# SY8029AIC-SCH.net
KiCad netlist of a schematic drawn in Altium Designer
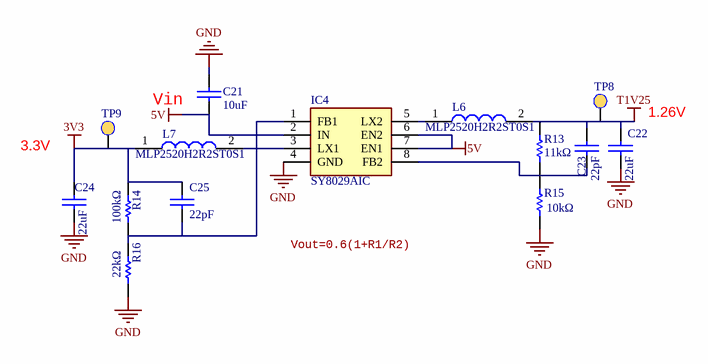
[diagram p0: SY8029AIC-SCH.SchDoc]

(export (version "E")
  (design (tool "Eeschema 10.0.6"))
  (components
    (comp (ref "C21")
      (value "10uF")
      (footprint "C_0805")
      (description "贴片电容")
      (fields (field (name "MANUFACTURER_PART_NUMBER") "±10% /25V"))
      (libsource (lib "IntLib-Passive") (part "Cap_Chip"))
    )
    (comp (ref "C22")
      (value "22uF")
      (footprint "C_0603")
      (description "贴片电容")
      (fields (field (name "MANUFACTURER_PART_NUMBER") "±10% /25V"))
      (libsource (lib "IntLib-Passive") (part "Cap_Chip"))
    )
    (comp (ref "C23")
      (value "22pF")
      (footprint "C_0402")
      (description "贴片电容")
      (fields (field (name "MANUFACTURER_PART_NUMBER") "±10% /25V"))
      (libsource (lib "IntLib-Passive") (part "Cap_Chip"))
    )
    (comp (ref "C24")
      (value "22uF")
      (footprint "C_0603")
      (description "贴片电容")
      (fields (field (name "MANUFACTURER_PART_NUMBER") "±10% /25V"))
      (libsource (lib "IntLib-Passive") (part "Cap_Chip"))
    )
    (comp (ref "C25")
      (value "22pF")
      (footprint "C_0402")
      (description "贴片电容")
      (fields (field (name "MANUFACTURER_PART_NUMBER") "±10% /25V"))
      (libsource (lib "IntLib-Passive") (part "Cap_Chip"))
    )
    (comp (ref "IC4")
      (value "SY8029AIC")
      (footprint "SOT23-8")
      (description "DC-DC降压芯片")
      (libsource (lib "IntLib-IC") (part "SY8029AIC"))
    )
    (comp (ref "L6")
      (value "MLP2520H2R2ST0S1")
      (footprint "INDC2520X100N")
      (description "Inductor")
      (fields (field (name "MANUFACTURER_PART_NUMBER") "MLP2520K1R0MT0S1"))
      (libsource (lib "*") (part "MLP2520K1R0MT0S1"))
    )
    (comp (ref "L7")
      (value "MLP2520H2R2ST0S1")
      (footprint "INDC2520X100N")
      (description "Inductor")
      (fields (field (name "MANUFACTURER_PART_NUMBER") "MLP2520K1R0MT0S1"))
      (libsource (lib "*") (part "MLP2520K1R0MT0S1"))
    )
    (comp (ref "R13")
      (value "11kΩ")
      (footprint "R_0402")
      (description "贴片电阻")
      (fields (field (name "MANUFACTURER_PART_NUMBER") "±1%"))
      (libsource (lib "IntLib-Passive") (part "Res_Chip"))
    )
    (comp (ref "R14")
      (value "100kΩ")
      (footprint "R_0402")
      (description "贴片电阻")
      (fields (field (name "MANUFACTURER_PART_NUMBER") "±1%"))
      (libsource (lib "IntLib-Passive") (part "Res_Chip"))
    )
    (comp (ref "R15")
      (value "10kΩ")
      (footprint "R_0402")
      (description "贴片电阻")
      (fields (field (name "MANUFACTURER_PART_NUMBER") "±1%"))
      (libsource (lib "IntLib-Passive") (part "Res_Chip"))
    )
    (comp (ref "R16")
      (value "22kΩ")
      (footprint "R_0402")
      (description "贴片电阻")
      (fields (field (name "MANUFACTURER_PART_NUMBER") "±1%"))
      (libsource (lib "IntLib-Passive") (part "Res_Chip"))
    )
    (comp (ref "TP8")
      (value "TP")
      (footprint "TP1.4mm")
      (description "测试点")
      (libsource (lib "MiscParts") (part "TP"))
    )
    (comp (ref "TP9")
      (value "TP")
      (footprint "TP1.4mm")
      (description "测试点")
      (libsource (lib "MiscParts") (part "TP"))
    )
  )
  (nets
    (net (code "1") (name "3V3") (class "Default")
      (node (ref "C24") (pin "1") (pinfunction "1_1") (pintype "passive"))
      (node (ref "C25") (pin "2") (pinfunction "2_2") (pintype "passive"))
      (node (ref "L7") (pin "1") (pinfunction "1_1") (pintype "passive"))
      (node (ref "R14") (pin "1") (pinfunction "1_1") (pintype "passive"))
      (node (ref "TP9") (pin "1") (pinfunction "TP_1") (pintype "passive"))
    )
    (net (code "2") (name "5V") (class "Default")
      (node (ref "C21") (pin "1") (pinfunction "1_1") (pintype "passive"))
      (node (ref "IC4") (pin "2") (pinfunction "IN_2") (pintype "passive"))
      (node (ref "IC4") (pin "6") (pinfunction "EN2_6") (pintype "passive"))
      (node (ref "IC4") (pin "7") (pinfunction "EN1_7") (pintype "passive"))
    )
    (net (code "3") (name "GND") (class "Default")
      (node (ref "C21") (pin "2") (pinfunction "2_2") (pintype "passive"))
      (node (ref "C22") (pin "2") (pinfunction "2_2") (pintype "passive"))
      (node (ref "C24") (pin "2") (pinfunction "2_2") (pintype "passive"))
      (node (ref "IC4") (pin "4") (pinfunction "GND_4") (pintype "passive"))
      (node (ref "R15") (pin "1") (pinfunction "1_1") (pintype "passive"))
      (node (ref "R16") (pin "2") (pinfunction "2_2") (pintype "passive"))
    )
    (net (code "4") (name "Net-(IC4-FB1)") (class "Default")
      (node (ref "C25") (pin "1") (pinfunction "1_1") (pintype "passive"))
      (node (ref "IC4") (pin "1") (pinfunction "FB1_1") (pintype "passive"))
      (node (ref "R14") (pin "2") (pinfunction "2_2") (pintype "passive"))
      (node (ref "R16") (pin "1") (pinfunction "1_1") (pintype "passive"))
    )
    (net (code "5") (name "Net-(IC4-FB2)") (class "Default")
      (node (ref "C23") (pin "2") (pinfunction "2_2") (pintype "passive"))
      (node (ref "IC4") (pin "8") (pinfunction "FB2_8") (pintype "passive"))
      (node (ref "R13") (pin "1") (pinfunction "1_1") (pintype "passive"))
      (node (ref "R15") (pin "2") (pinfunction "2_2") (pintype "passive"))
    )
    (net (code "6") (name "Net-(IC4-LX1)") (class "Default")
      (node (ref "IC4") (pin "3") (pinfunction "LX1_3") (pintype "passive"))
      (node (ref "L7") (pin "2") (pinfunction "2_2") (pintype "passive"))
    )
    (net (code "7") (name "Net-(IC4-LX2)") (class "Default")
      (node (ref "IC4") (pin "5") (pinfunction "LX2_5") (pintype "passive"))
      (node (ref "L6") (pin "1") (pinfunction "1_1") (pintype "passive"))
    )
    (net (code "8") (name "T1V25") (class "Default")
      (node (ref "C22") (pin "1") (pinfunction "1_1") (pintype "passive"))
      (node (ref "C23") (pin "1") (pinfunction "1_1") (pintype "passive"))
      (node (ref "L6") (pin "2") (pinfunction "2_2") (pintype "passive"))
      (node (ref "R13") (pin "2") (pinfunction "2_2") (pintype "passive"))
      (node (ref "TP8") (pin "1") (pinfunction "TP_1") (pintype "passive"))
    )
  )
)
